# PAGE2_-MCU.net
KiCad netlist of a schematic drawn in Altium Designer
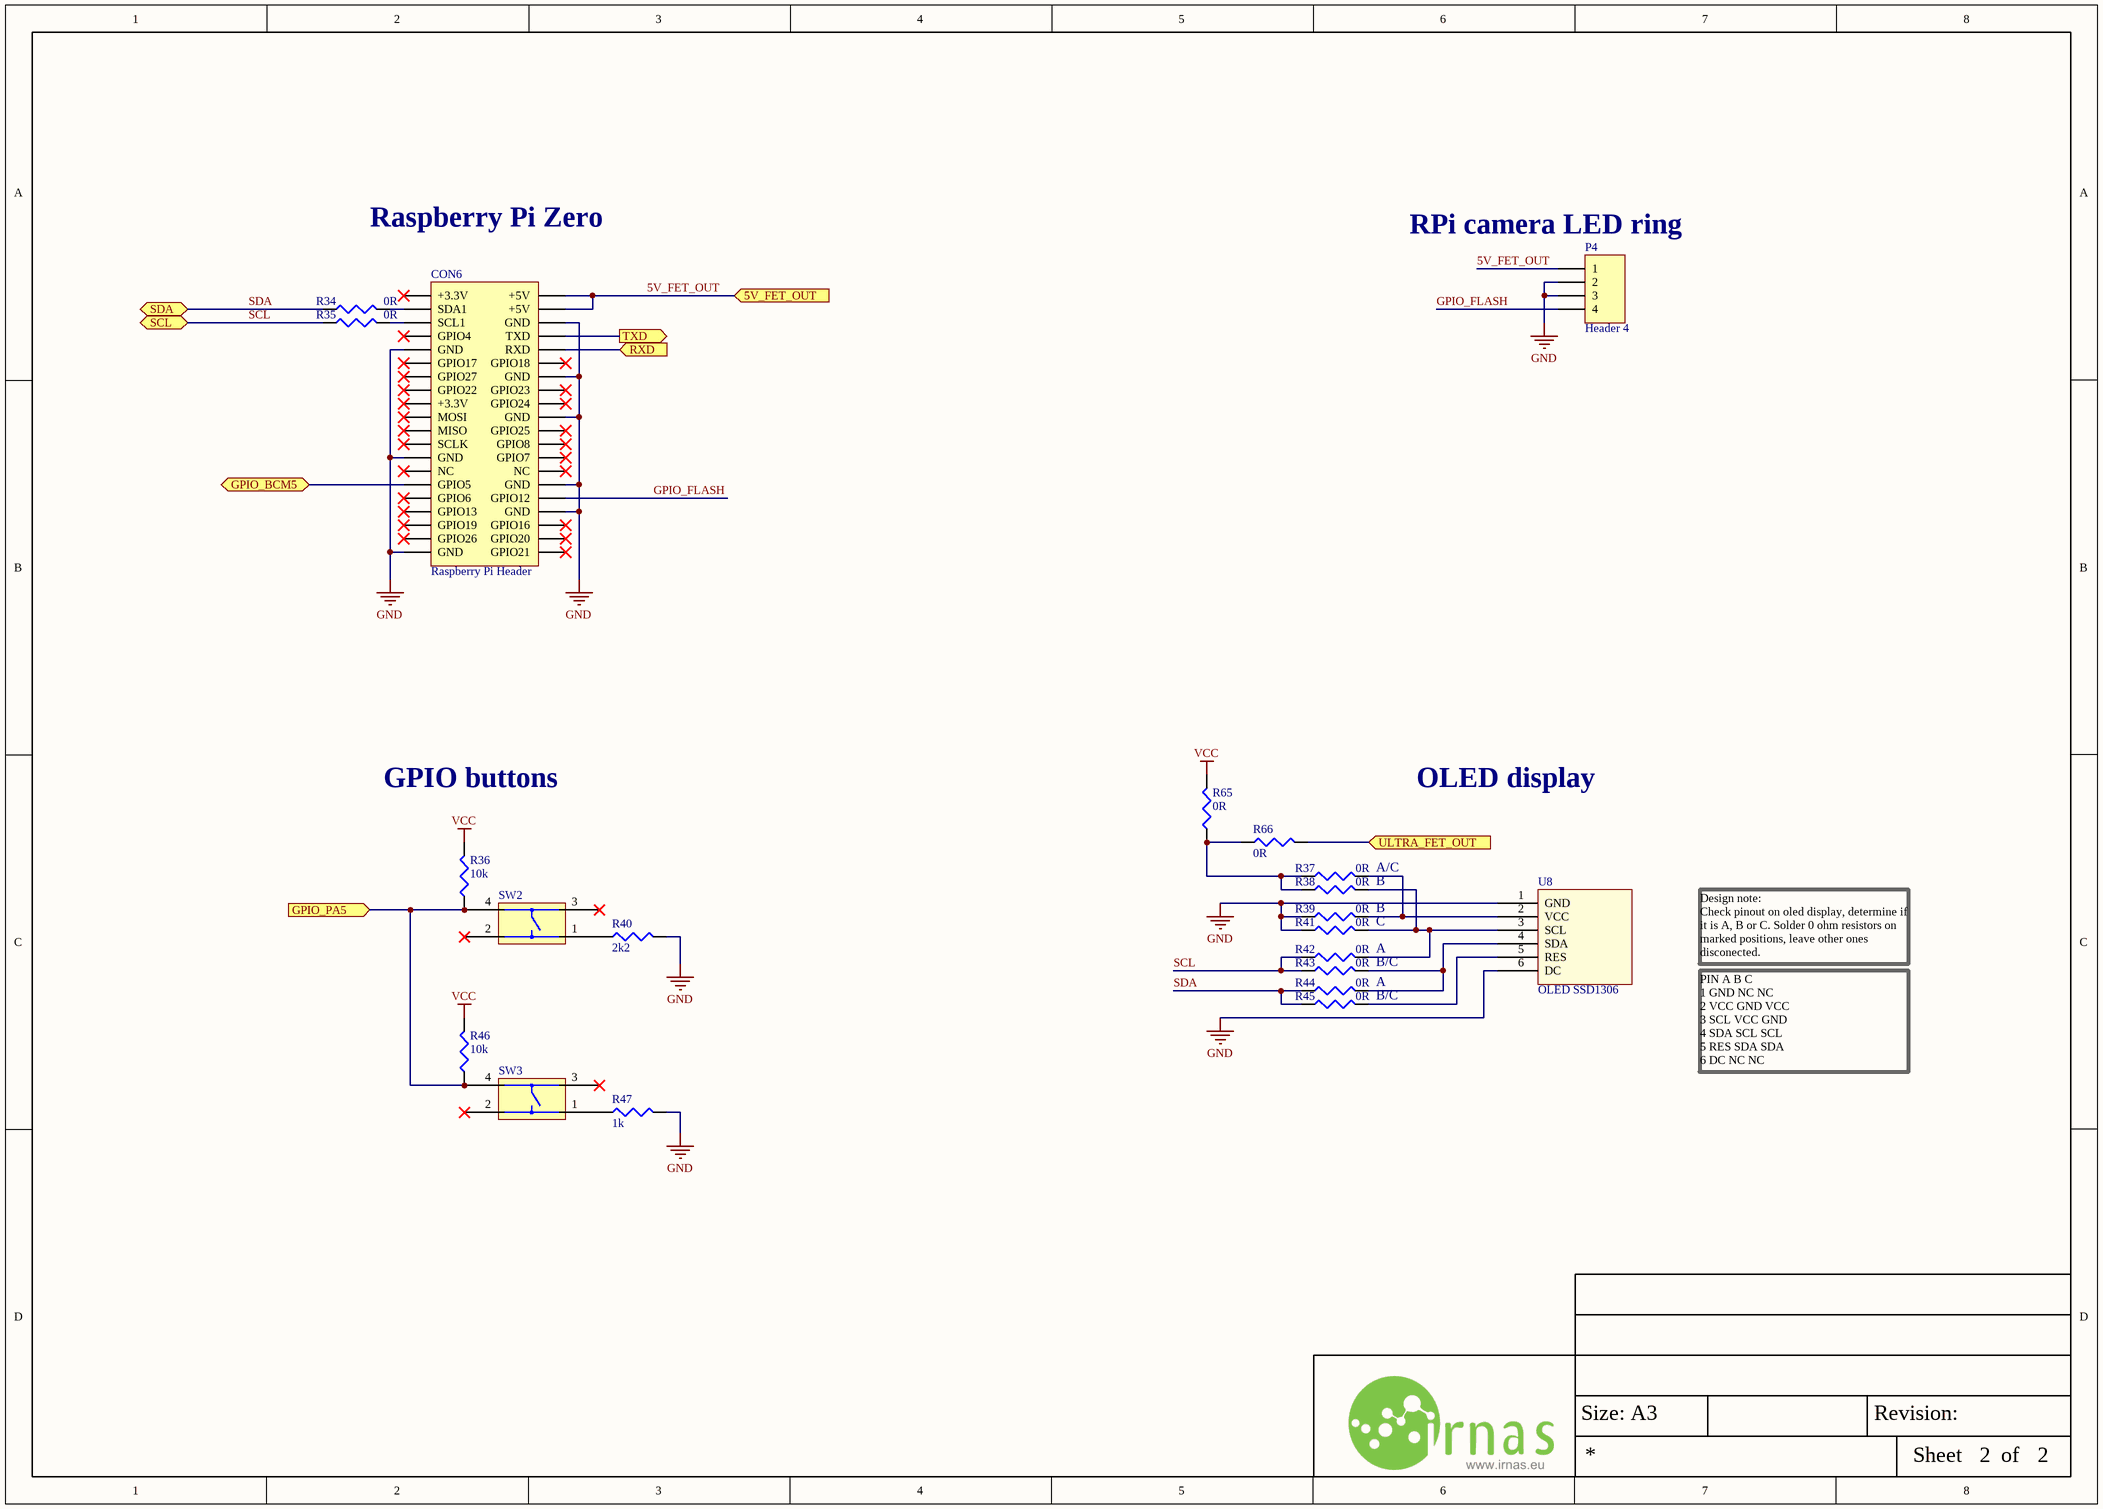
[diagram p0: PAGE2 -MCU.SchDoc]

(export (version "E")
  (design (tool "Eeschema 10.0.6"))
  (components
    (comp (ref "CON6")
      (value "Raspberry Pi Header")
      (footprint "Connectors:HDR2X20")
      (description "Header, 20-Pin, Dual row")
      (fields (field (name "PUBLISHER") "Altium Limited"))
      (libsource (lib "Connectors") (part "Raspberry Pi Header"))
    )
    (comp (ref "P4")
      (value "Header 4")
      (footprint "HDR1X4")
      (description "Header, 4-Pin")
      (fields (field (name "PUBLISHER") "Altium Limited"))
      (libsource (lib "Miscellaneous Connectors") (part "Header 4"))
    )
    (comp (ref "R34")
      (value "0R")
      (footprint "RES0603")
      (description "BOURNS - CR0603-J/-000ELF - RES, THICK FILM, 0R, 5%, 0.1W, 0603")
      (fields
        (field (name "MANUFACTURER") "BOURNS")
        (field (name "MANUFACTURER PART NUMBER") "CR0603-J/-000ELF")
      )
      (libsource (lib "Passive") (part "R - 0R"))
    )
    (comp (ref "R35")
      (value "0R")
      (footprint "RES0603")
      (description "BOURNS - CR0603-J/-000ELF - RES, THICK FILM, 0R, 5%, 0.1W, 0603")
      (fields
        (field (name "MANUFACTURER") "BOURNS")
        (field (name "MANUFACTURER PART NUMBER") "CR0603-J/-000ELF")
      )
      (libsource (lib "Passive") (part "R - 0R"))
    )
    (comp (ref "R36")
      (value "10k")
      (footprint "RES0603")
      (description "MULTICOMP - MCMR06X103 JTL - RES, CERAMIC, 10K, 5%, 0.1W, 0603")
      (fields
        (field (name "MANUFACTURER") "MULTICOMP")
        (field (name "MANUFACTURER PART NUMBER") "MCMR06X103 JTL")
      )
      (libsource (lib "Passive") (part "R - 10k"))
    )
    (comp (ref "R37")
      (value "0R")
      (footprint "RES0603")
      (description "BOURNS - CR0603-J/-000ELF - RES, THICK FILM, 0R, 5%, 0.1W, 0603")
      (fields
        (field (name "MANUFACTURER") "BOURNS")
        (field (name "MANUFACTURER PART NUMBER") "CR0603-J/-000ELF")
      )
      (libsource (lib "Passive") (part "R - 0R"))
    )
    (comp (ref "R38")
      (value "0R")
      (footprint "RES0603")
      (description "BOURNS - CR0603-J/-000ELF - RES, THICK FILM, 0R, 5%, 0.1W, 0603")
      (fields
        (field (name "MANUFACTURER") "BOURNS")
        (field (name "MANUFACTURER PART NUMBER") "CR0603-J/-000ELF")
      )
      (libsource (lib "Passive") (part "R - 0R"))
    )
    (comp (ref "R39")
      (value "0R")
      (footprint "RES0603")
      (description "BOURNS - CR0603-J/-000ELF - RES, THICK FILM, 0R, 5%, 0.1W, 0603")
      (fields
        (field (name "MANUFACTURER") "BOURNS")
        (field (name "MANUFACTURER PART NUMBER") "CR0603-J/-000ELF")
      )
      (libsource (lib "Passive") (part "R - 0R"))
    )
    (comp (ref "R40")
      (value "2k2")
      (footprint "RES0603")
      (description "MULTICOMP - MCMR06X2201FTL - RES, CERAMIC, 2K2, 1%, 0.1W, 0603")
      (fields
        (field (name "MANUFACTURER") "MULTICOMP")
        (field (name "MANUFACTURER PART NUMBER") "MCMR06X2201FTL")
      )
      (libsource (lib "Passive") (part "R - 2k2"))
    )
    (comp (ref "R41")
      (value "0R")
      (footprint "RES0603")
      (description "BOURNS - CR0603-J/-000ELF - RES, THICK FILM, 0R, 5%, 0.1W, 0603")
      (fields
        (field (name "MANUFACTURER") "BOURNS")
        (field (name "MANUFACTURER PART NUMBER") "CR0603-J/-000ELF")
      )
      (libsource (lib "Passive") (part "R - 0R"))
    )
    (comp (ref "R42")
      (value "0R")
      (footprint "RES0603")
      (description "BOURNS - CR0603-J/-000ELF - RES, THICK FILM, 0R, 5%, 0.1W, 0603")
      (fields
        (field (name "MANUFACTURER") "BOURNS")
        (field (name "MANUFACTURER PART NUMBER") "CR0603-J/-000ELF")
      )
      (libsource (lib "Passive") (part "R - 0R"))
    )
    (comp (ref "R43")
      (value "0R")
      (footprint "RES0603")
      (description "BOURNS - CR0603-J/-000ELF - RES, THICK FILM, 0R, 5%, 0.1W, 0603")
      (fields
        (field (name "MANUFACTURER") "BOURNS")
        (field (name "MANUFACTURER PART NUMBER") "CR0603-J/-000ELF")
      )
      (libsource (lib "Passive") (part "R - 0R"))
    )
    (comp (ref "R44")
      (value "0R")
      (footprint "RES0603")
      (description "BOURNS - CR0603-J/-000ELF - RES, THICK FILM, 0R, 5%, 0.1W, 0603")
      (fields
        (field (name "MANUFACTURER") "BOURNS")
        (field (name "MANUFACTURER PART NUMBER") "CR0603-J/-000ELF")
      )
      (libsource (lib "Passive") (part "R - 0R"))
    )
    (comp (ref "R45")
      (value "0R")
      (footprint "RES0603")
      (description "BOURNS - CR0603-J/-000ELF - RES, THICK FILM, 0R, 5%, 0.1W, 0603")
      (fields
        (field (name "MANUFACTURER") "BOURNS")
        (field (name "MANUFACTURER PART NUMBER") "CR0603-J/-000ELF")
      )
      (libsource (lib "Passive") (part "R - 0R"))
    )
    (comp (ref "R46")
      (value "10k")
      (footprint "RES0603")
      (description "MULTICOMP - MCMR06X103 JTL - RES, CERAMIC, 10K, 5%, 0.1W, 0603")
      (fields
        (field (name "MANUFACTURER") "MULTICOMP")
        (field (name "MANUFACTURER PART NUMBER") "MCMR06X103 JTL")
      )
      (libsource (lib "Passive") (part "R - 10k"))
    )
    (comp (ref "R47")
      (value "1k")
      (footprint "RES0603")
      (description "MULTICOMP - MCMR06X102 JTL - RES, CERAMIC, 1K, 5%, 0.1W, 0603")
      (fields
        (field (name "MANUFACTURER") "MULTICOMP")
        (field (name "MANUFACTURER PART NUMBER") "MCMR06X102 JTL")
      )
      (libsource (lib "Passive") (part "R - 1k"))
    )
    (comp (ref "R65")
      (value "0R")
      (footprint "RES0603")
      (description "BOURNS - CR0603-J/-000ELF - RES, THICK FILM, 0R, 5%, 0.1W, 0603")
      (fields
        (field (name "MANUFACTURER") "BOURNS")
        (field (name "MANUFACTURER PART NUMBER") "CR0603-J/-000ELF")
      )
      (libsource (lib "Passive") (part "R - 0R"))
    )
    (comp (ref "R66")
      (value "0R")
      (footprint "RES0603")
      (description "BOURNS - CR0603-J/-000ELF - RES, THICK FILM, 0R, 5%, 0.1W, 0603")
      (fields
        (field (name "MANUFACTURER") "BOURNS")
        (field (name "MANUFACTURER PART NUMBER") "CR0603-J/-000ELF")
      )
      (libsource (lib "Passive") (part "R - 0R"))
    )
    (comp (ref "SW2")
      (value "BTN - B3F-1070")
      (footprint "BTN B3F-1070")
      (description "Tactile Switch, B3F Series, Top Actuated, Through Hole, Round Button, 100 gf, 50mA at 24VDC")
      (libsource (lib "Mechanical") (part "BTN - B3F-1070"))
    )
    (comp (ref "SW3")
      (value "BTN - B3F-1070")
      (footprint "BTN B3F-1070")
      (description "Tactile Switch, B3F Series, Top Actuated, Through Hole, Round Button, 100 gf, 50mA at 24VDC")
      (libsource (lib "Mechanical") (part "BTN - B3F-1070"))
    )
    (comp (ref "U8")
      (value "OLED SSD1306")
      (footprint "OLED SSD1306")
      (libsource (lib "oled") (part "OLED SSD1306"))
    )
  )
  (nets
    (net (code "1") (name "/5V_FET_OUT") (class "Default")
      (node (ref "CON6") (pin "2") (pinfunction "+5V_2") (pintype "passive"))
      (node (ref "CON6") (pin "4") (pinfunction "+5V_4") (pintype "passive"))
      (node (ref "P4") (pin "1") (pinfunction "1_1") (pintype "passive"))
    )
    (net (code "2") (name "/GPIO_BCM5") (class "Default")
      (node (ref "CON6") (pin "29") (pinfunction "GPIO5_29") (pintype "passive"))
    )
    (net (code "3") (name "/GPIO_FLASH") (class "Default")
      (node (ref "CON6") (pin "32") (pinfunction "GPIO12_32") (pintype "passive"))
      (node (ref "P4") (pin "4") (pinfunction "4_4") (pintype "passive"))
    )
    (net (code "4") (name "/GPIO_PA5") (class "Default")
      (node (ref "R36") (pin "1") (pinfunction "1_1") (pintype "passive"))
      (node (ref "R46") (pin "1") (pinfunction "1_1") (pintype "passive"))
      (node (ref "SW2") (pin "4") (pinfunction "4_4") (pintype "passive"))
      (node (ref "SW3") (pin "4") (pinfunction "4_4") (pintype "passive"))
    )
    (net (code "5") (name "/RXD") (class "Default")
      (node (ref "CON6") (pin "10") (pinfunction "RXD_10") (pintype "passive"))
    )
    (net (code "6") (name "/SCL") (class "Default")
      (node (ref "R35") (pin "1") (pinfunction "1_1") (pintype "passive"))
      (node (ref "R42") (pin "1") (pinfunction "1_1") (pintype "passive"))
      (node (ref "R43") (pin "1") (pinfunction "1_1") (pintype "passive"))
    )
    (net (code "7") (name "/SDA") (class "Default")
      (node (ref "R34") (pin "1") (pinfunction "1_1") (pintype "passive"))
      (node (ref "R44") (pin "1") (pinfunction "1_1") (pintype "passive"))
      (node (ref "R45") (pin "1") (pinfunction "1_1") (pintype "passive"))
    )
    (net (code "8") (name "/TXD") (class "Default")
      (node (ref "CON6") (pin "8") (pinfunction "TXD_8") (pintype "passive"))
    )
    (net (code "9") (name "/ULTRA_FET_OUT") (class "Default")
      (node (ref "R66") (pin "2") (pinfunction "2_2") (pintype "passive"))
    )
    (net (code "10") (name "GND") (class "Default")
      (node (ref "CON6") (pin "14") (pinfunction "GND_14") (pintype "passive"))
      (node (ref "CON6") (pin "20") (pinfunction "GND_20") (pintype "passive"))
      (node (ref "CON6") (pin "25") (pinfunction "GND_25") (pintype "passive"))
      (node (ref "CON6") (pin "30") (pinfunction "GND_30") (pintype "passive"))
      (node (ref "CON6") (pin "34") (pinfunction "GND_34") (pintype "passive"))
      (node (ref "CON6") (pin "39") (pinfunction "GND_39") (pintype "passive"))
      (node (ref "CON6") (pin "6") (pinfunction "GND_6") (pintype "passive"))
      (node (ref "CON6") (pin "9") (pinfunction "GND_9") (pintype "passive"))
      (node (ref "P4") (pin "2") (pinfunction "2_2") (pintype "passive"))
      (node (ref "P4") (pin "3") (pinfunction "3_3") (pintype "passive"))
      (node (ref "R39") (pin "1") (pinfunction "1_1") (pintype "passive"))
      (node (ref "R40") (pin "2") (pinfunction "2_2") (pintype "passive"))
      (node (ref "R41") (pin "1") (pinfunction "1_1") (pintype "passive"))
      (node (ref "R47") (pin "2") (pinfunction "2_2") (pintype "passive"))
      (node (ref "U8") (pin "1") (pinfunction "GND_1") (pintype "passive"))
      (node (ref "U8") (pin "6") (pinfunction "DC_6") (pintype "passive"))
    )
    (net (code "11") (name "Net-(CON6-SCL1)") (class "Default")
      (node (ref "CON6") (pin "5") (pinfunction "SCL1_5") (pintype "passive"))
      (node (ref "R35") (pin "2") (pinfunction "2_2") (pintype "passive"))
    )
    (net (code "12") (name "Net-(CON6-SDA1)") (class "Default")
      (node (ref "CON6") (pin "3") (pinfunction "SDA1_3") (pintype "passive"))
      (node (ref "R34") (pin "2") (pinfunction "2_2") (pintype "passive"))
    )
    (net (code "13") (name "Net-(R37-Pad1)") (class "Default")
      (node (ref "R37") (pin "1") (pinfunction "1_1") (pintype "passive"))
      (node (ref "R38") (pin "1") (pinfunction "1_1") (pintype "passive"))
      (node (ref "R65") (pin "1") (pinfunction "1_1") (pintype "passive"))
      (node (ref "R66") (pin "1") (pinfunction "1_1") (pintype "passive"))
    )
    (net (code "14") (name "Net-(R40-Pad1)") (class "Default")
      (node (ref "R40") (pin "1") (pinfunction "1_1") (pintype "passive"))
      (node (ref "SW2") (pin "1") (pinfunction "1_1") (pintype "passive"))
    )
    (net (code "15") (name "Net-(R47-Pad1)") (class "Default")
      (node (ref "R47") (pin "1") (pinfunction "1_1") (pintype "passive"))
      (node (ref "SW3") (pin "1") (pinfunction "1_1") (pintype "passive"))
    )
    (net (code "16") (name "Net-(U8-RES)") (class "Default")
      (node (ref "R45") (pin "2") (pinfunction "2_2") (pintype "passive"))
      (node (ref "U8") (pin "5") (pinfunction "RES_5") (pintype "passive"))
    )
    (net (code "17") (name "Net-(U8-SCL)") (class "Default")
      (node (ref "R38") (pin "2") (pinfunction "2_2") (pintype "passive"))
      (node (ref "R41") (pin "2") (pinfunction "2_2") (pintype "passive"))
      (node (ref "R42") (pin "2") (pinfunction "2_2") (pintype "passive"))
      (node (ref "U8") (pin "3") (pinfunction "SCL_3") (pintype "passive"))
    )
    (net (code "18") (name "Net-(U8-SDA)") (class "Default")
      (node (ref "R43") (pin "2") (pinfunction "2_2") (pintype "passive"))
      (node (ref "R44") (pin "2") (pinfunction "2_2") (pintype "passive"))
      (node (ref "U8") (pin "4") (pinfunction "SDA_4") (pintype "passive"))
    )
    (net (code "19") (name "Net-(U8-VCC)") (class "Default")
      (node (ref "R37") (pin "2") (pinfunction "2_2") (pintype "passive"))
      (node (ref "R39") (pin "2") (pinfunction "2_2") (pintype "passive"))
      (node (ref "U8") (pin "2") (pinfunction "VCC_2") (pintype "passive"))
    )
    (net (code "20") (name "VCC") (class "Default")
      (node (ref "R36") (pin "2") (pinfunction "2_2") (pintype "passive"))
      (node (ref "R46") (pin "2") (pinfunction "2_2") (pintype "passive"))
      (node (ref "R65") (pin "2") (pinfunction "2_2") (pintype "passive"))
    )
    (net (code "21") (name "unconnected-(CON6-+3.3V-Pad1)") (class "Default")
      (node (ref "CON6") (pin "1") (pinfunction "+3.3V_1") (pintype "passive+no_connect"))
    )
    (net (code "22") (name "unconnected-(CON6-+3.3V-Pad17)") (class "Default")
      (node (ref "CON6") (pin "17") (pinfunction "+3.3V_17") (pintype "passive+no_connect"))
    )
    (net (code "23") (name "unconnected-(CON6-GPIO4-Pad7)") (class "Default")
      (node (ref "CON6") (pin "7") (pinfunction "GPIO4_7") (pintype "passive+no_connect"))
    )
    (net (code "24") (name "unconnected-(CON6-GPIO6-Pad31)") (class "Default")
      (node (ref "CON6") (pin "31") (pinfunction "GPIO6_31") (pintype "passive+no_connect"))
    )
    (net (code "25") (name "unconnected-(CON6-GPIO7-Pad26)") (class "Default")
      (node (ref "CON6") (pin "26") (pinfunction "GPIO7_26") (pintype "passive+no_connect"))
    )
    (net (code "26") (name "unconnected-(CON6-GPIO8-Pad24)") (class "Default")
      (node (ref "CON6") (pin "24") (pinfunction "GPIO8_24") (pintype "passive+no_connect"))
    )
    (net (code "27") (name "unconnected-(CON6-GPIO13-Pad33)") (class "Default")
      (node (ref "CON6") (pin "33") (pinfunction "GPIO13_33") (pintype "passive+no_connect"))
    )
    (net (code "28") (name "unconnected-(CON6-GPIO16-Pad36)") (class "Default")
      (node (ref "CON6") (pin "36") (pinfunction "GPIO16_36") (pintype "passive+no_connect"))
    )
    (net (code "29") (name "unconnected-(CON6-GPIO17-Pad11)") (class "Default")
      (node (ref "CON6") (pin "11") (pinfunction "GPIO17_11") (pintype "passive+no_connect"))
    )
    (net (code "30") (name "unconnected-(CON6-GPIO18-Pad12)") (class "Default")
      (node (ref "CON6") (pin "12") (pinfunction "GPIO18_12") (pintype "passive+no_connect"))
    )
    (net (code "31") (name "unconnected-(CON6-GPIO19-Pad35)") (class "Default")
      (node (ref "CON6") (pin "35") (pinfunction "GPIO19_35") (pintype "passive+no_connect"))
    )
    (net (code "32") (name "unconnected-(CON6-GPIO20-Pad38)") (class "Default")
      (node (ref "CON6") (pin "38") (pinfunction "GPIO20_38") (pintype "passive+no_connect"))
    )
    (net (code "33") (name "unconnected-(CON6-GPIO21-Pad40)") (class "Default")
      (node (ref "CON6") (pin "40") (pinfunction "GPIO21_40") (pintype "passive+no_connect"))
    )
    (net (code "34") (name "unconnected-(CON6-GPIO22-Pad15)") (class "Default")
      (node (ref "CON6") (pin "15") (pinfunction "GPIO22_15") (pintype "passive+no_connect"))
    )
    (net (code "35") (name "unconnected-(CON6-GPIO23-Pad16)") (class "Default")
      (node (ref "CON6") (pin "16") (pinfunction "GPIO23_16") (pintype "passive+no_connect"))
    )
    (net (code "36") (name "unconnected-(CON6-GPIO24-Pad18)") (class "Default")
      (node (ref "CON6") (pin "18") (pinfunction "GPIO24_18") (pintype "passive+no_connect"))
    )
    (net (code "37") (name "unconnected-(CON6-GPIO25-Pad22)") (class "Default")
      (node (ref "CON6") (pin "22") (pinfunction "GPIO25_22") (pintype "passive+no_connect"))
    )
    (net (code "38") (name "unconnected-(CON6-GPIO26-Pad37)") (class "Default")
      (node (ref "CON6") (pin "37") (pinfunction "GPIO26_37") (pintype "passive+no_connect"))
    )
    (net (code "39") (name "unconnected-(CON6-GPIO27-Pad13)") (class "Default")
      (node (ref "CON6") (pin "13") (pinfunction "GPIO27_13") (pintype "passive+no_connect"))
    )
    (net (code "40") (name "unconnected-(CON6-MISO-Pad21)") (class "Default")
      (node (ref "CON6") (pin "21") (pinfunction "MISO_21") (pintype "passive+no_connect"))
    )
    (net (code "41") (name "unconnected-(CON6-MOSI-Pad19)") (class "Default")
      (node (ref "CON6") (pin "19") (pinfunction "MOSI_19") (pintype "passive+no_connect"))
    )
    (net (code "42") (name "unconnected-(CON6-NC-Pad27)") (class "Default")
      (node (ref "CON6") (pin "27") (pinfunction "NC_27") (pintype "passive+no_connect"))
    )
    (net (code "43") (name "unconnected-(CON6-NC-Pad28)") (class "Default")
      (node (ref "CON6") (pin "28") (pinfunction "NC_28") (pintype "passive+no_connect"))
    )
    (net (code "44") (name "unconnected-(CON6-SCLK-Pad23)") (class "Default")
      (node (ref "CON6") (pin "23") (pinfunction "SCLK_23") (pintype "passive+no_connect"))
    )
    (net (code "45") (name "unconnected-(SW2-Pad2)") (class "Default")
      (node (ref "SW2") (pin "2") (pinfunction "2_2") (pintype "passive+no_connect"))
    )
    (net (code "46") (name "unconnected-(SW2-Pad3)") (class "Default")
      (node (ref "SW2") (pin "3") (pinfunction "3_3") (pintype "passive+no_connect"))
    )
    (net (code "47") (name "unconnected-(SW3-Pad2)") (class "Default")
      (node (ref "SW3") (pin "2") (pinfunction "2_2") (pintype "passive+no_connect"))
    )
    (net (code "48") (name "unconnected-(SW3-Pad3)") (class "Default")
      (node (ref "SW3") (pin "3") (pinfunction "3_3") (pintype "passive+no_connect"))
    )
  )
)
